# TopLevel.net
KiCad netlist of a schematic drawn in Altium Designer
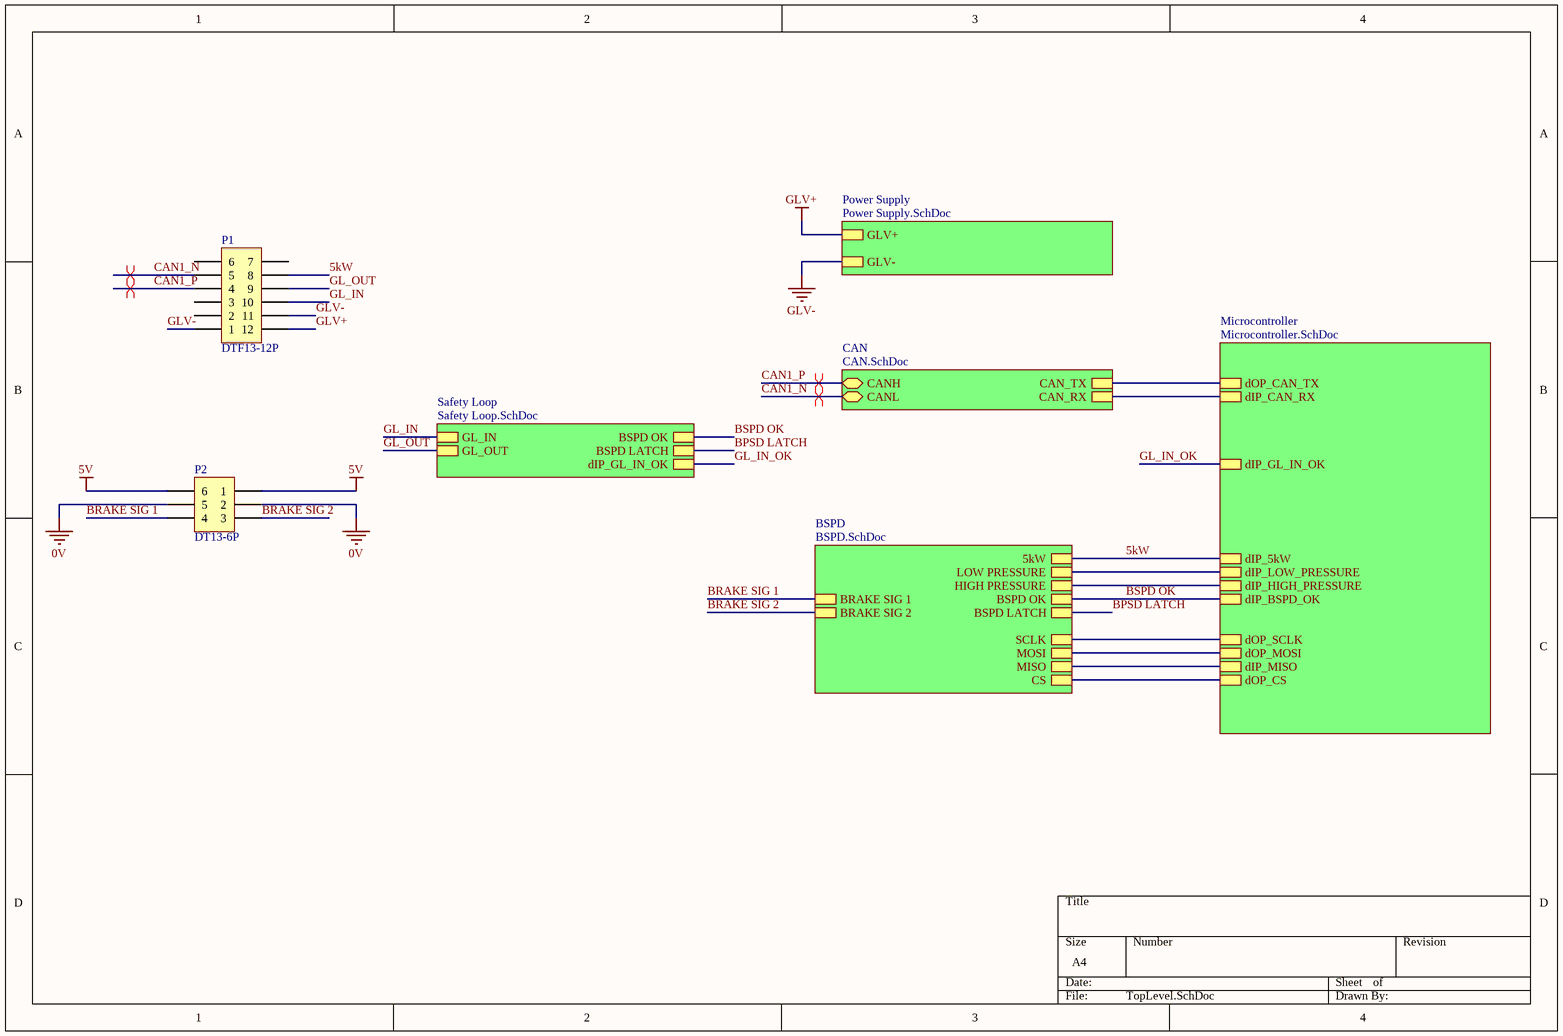
[diagram p0: TopLevel.SchDoc]

(export (version "E")
  (design (tool "Eeschema 10.0.6"))
  (components
    (comp (ref "P1")
      (value "DTF13-12P")
      (footprint "DTF13-12P")
      (fields (field (name "DIGIKEY PART NUMBER") "1734-1861-ND") (field (name "CONTACT") "Copper Alloy"))
      (libsource (lib "ts_standard_connectors") (part "DT13-12P"))
    )
    (comp (ref "P2")
      (value "DT13-6P")
      (footprint "DTF13-6P")
      (fields
        (field (name "PART NUMBER") "DTF13-6P")
        (field (name "DIGIKEY PART NUMBER") "1734-1754-ND")
        (field (name "CONTACT") "Copper Alloy")
      )
      (libsource (lib "ts_standard_connectors") (part "DT13-6P"))
    )
  )
  (nets
    (net (code "1") (name "/5kW") (class "Default")
      (node (ref "P1") (pin "8") (pinfunction "8_8") (pintype "passive"))
    )
    (net (code "3") (name "/BRAKE SIG 1") (class "Default")
      (node (ref "P2") (pin "4") (pinfunction "4_4") (pintype "passive"))
    )
    (net (code "4") (name "/BRAKE SIG 2") (class "Default")
      (node (ref "P2") (pin "3") (pinfunction "3_3") (pintype "power_in"))
    )
    (net (code "6") (name "/CAN1_N") (class "Default")
      (node (ref "P1") (pin "5") (pinfunction "5_5") (pintype "power_in"))
    )
    (net (code "7") (name "/CAN1_P") (class "Default")
      (node (ref "P1") (pin "4") (pinfunction "4_4") (pintype "power_in"))
    )
    (net (code "11") (name "/GL_IN") (class "Default")
      (node (ref "P1") (pin "10") (pinfunction "10_10") (pintype "passive"))
    )
    (net (code "13") (name "/GL_OUT") (class "Default")
      (node (ref "P1") (pin "9") (pinfunction "9_9") (pintype "passive"))
    )
    (net (code "19") (name "0V") (class "Default")
      (node (ref "P2") (pin "2") (pinfunction "2_2") (pintype "power_in"))
      (node (ref "P2") (pin "5") (pinfunction "5_5") (pintype "passive"))
    )
    (net (code "20") (name "5V") (class "Default")
      (node (ref "P2") (pin "1") (pinfunction "1_1") (pintype "power_in"))
      (node (ref "P2") (pin "6") (pinfunction "6_6") (pintype "passive"))
    )
    (net (code "21") (name "GLV+") (class "Default")
      (node (ref "P1") (pin "12") (pinfunction "12_12") (pintype "passive"))
    )
    (net (code "22") (name "GLV-") (class "Default")
      (node (ref "P1") (pin "1") (pinfunction "1_1") (pintype "power_in"))
      (node (ref "P1") (pin "11") (pinfunction "11_11") (pintype "passive"))
    )
    (net (code "23") (name "unconnected-(P1-Pad2)") (class "Default")
      (node (ref "P1") (pin "2") (pinfunction "2_2") (pintype "power_in"))
    )
    (net (code "24") (name "unconnected-(P1-Pad3)") (class "Default")
      (node (ref "P1") (pin "3") (pinfunction "3_3") (pintype "power_in"))
    )
    (net (code "25") (name "unconnected-(P1-Pad6)") (class "Default")
      (node (ref "P1") (pin "6") (pinfunction "6_6") (pintype "power_in"))
    )
    (net (code "26") (name "unconnected-(P1-Pad7)") (class "Default")
      (node (ref "P1") (pin "7") (pinfunction "7_7") (pintype "passive"))
    )
  )
)
